# EPS_V1.net
KiCad netlist of a schematic drawn in Altium Designer
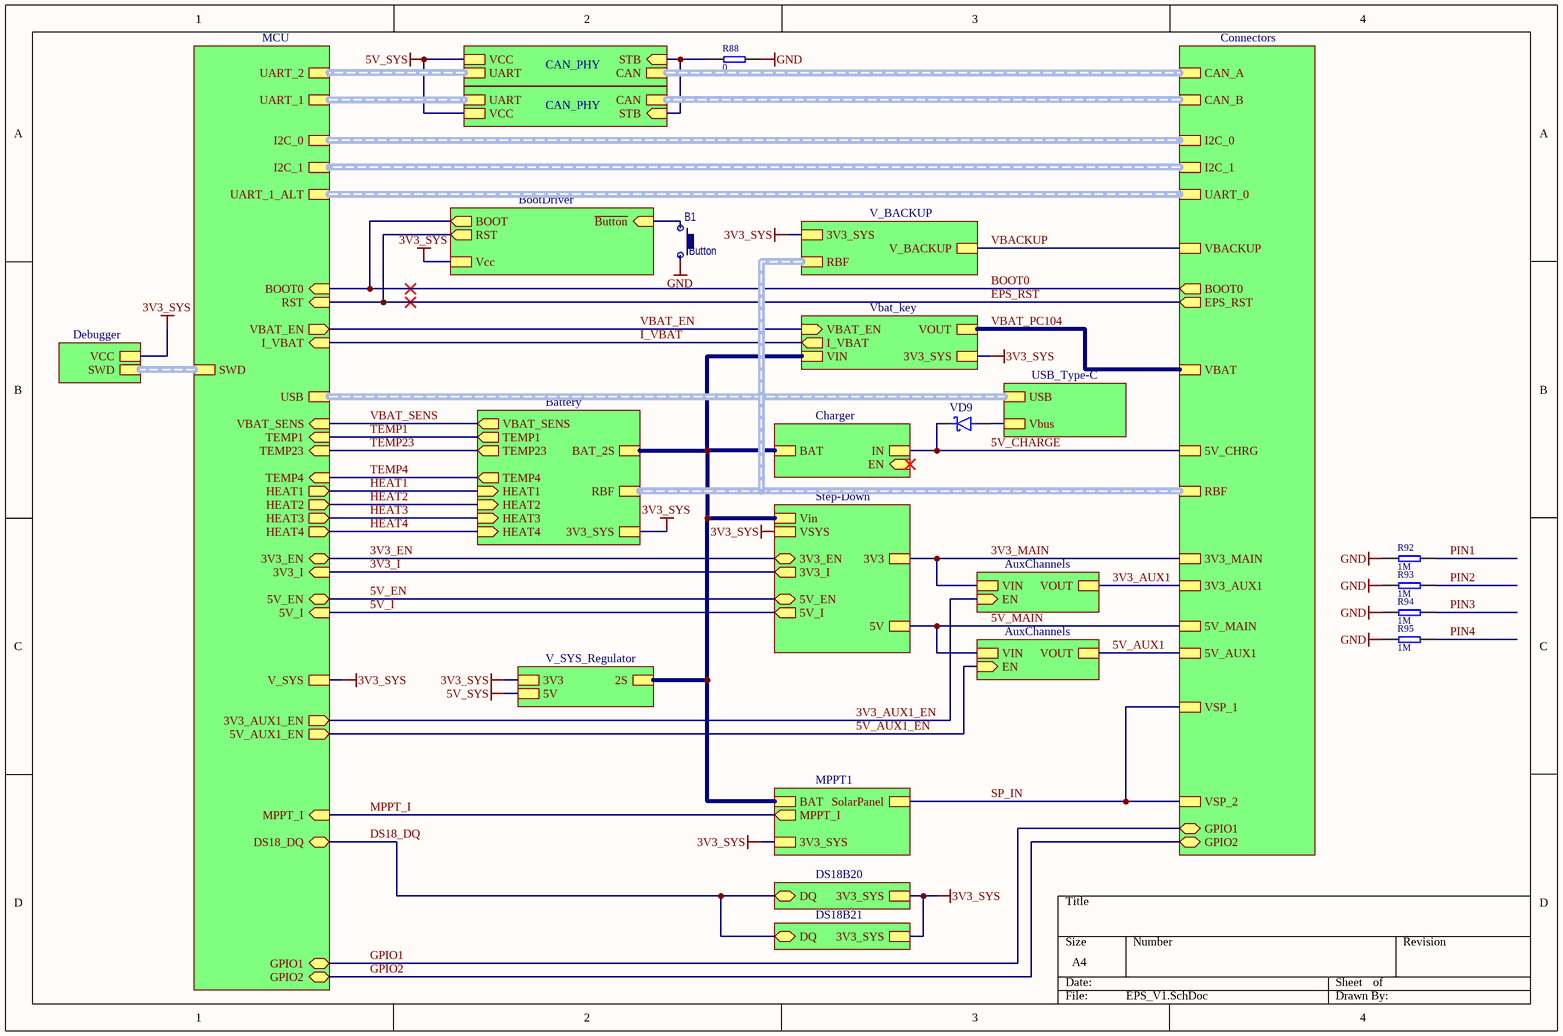
[diagram p0: EPS_V1.SchDoc]

(export (version "E")
  (design (tool "Eeschema 10.0.6"))
  (components
    (comp (ref "B1")
      (value "Button")
      (footprint "button")
      (libsource (lib "electromechanical") (part "Button"))
    )
    (comp (ref "R88")
      (value "0")
      (footprint "RES 0402")
      (description "Resistor")
      (fields (field (name "Comment") "RES 0402 0"))
      (libsource (lib "!main") (part "!Resistor"))
    )
    (comp (ref "R92")
      (value "1M")
      (footprint "RES 0402")
      (description "Resistor")
      (fields (field (name "Comment") "RES 0402 1M"))
      (libsource (lib "!main") (part "!Resistor"))
    )
    (comp (ref "R93")
      (value "1M")
      (footprint "RES 0402")
      (description "Resistor")
      (fields (field (name "Comment") "RES 0402 1M"))
      (libsource (lib "!main") (part "!Resistor"))
    )
    (comp (ref "R94")
      (value "1M")
      (footprint "RES 0402")
      (description "Resistor")
      (fields (field (name "Comment") "RES 0402 1M"))
      (libsource (lib "!main") (part "!Resistor"))
    )
    (comp (ref "R95")
      (value "1M")
      (footprint "RES 0402")
      (description "Resistor")
      (fields (field (name "Comment") "RES 0402 1M"))
      (libsource (lib "!main") (part "!Resistor"))
    )
    (comp (ref "VD9")
      (value "Shottly diode SOD-123")
      (footprint "SOD-123")
      (description "Diode Shottky")
      (libsource (lib "diodes") (part "DiodeS"))
    )
  )
  (nets
    (net (code "9") (name "/5V_CHARGE") (class "Default")
      (node (ref "VD9") (pin "C") (pinfunction "Cathode_C") (pintype "passive"))
    )
    (net (code "29") (name "/PIN1") (class "Default")
      (node (ref "R92") (pin "2") (pinfunction "12_2") (pintype "passive"))
    )
    (net (code "30") (name "/PIN2") (class "Default")
      (node (ref "R93") (pin "2") (pinfunction "12_2") (pintype "passive"))
    )
    (net (code "31") (name "/PIN3") (class "Default")
      (node (ref "R94") (pin "2") (pinfunction "12_2") (pintype "passive"))
    )
    (net (code "32") (name "/PIN4") (class "Default")
      (node (ref "R95") (pin "2") (pinfunction "12_2") (pintype "passive"))
    )
    (net (code "35") (name "/STB") (class "Default")
      (node (ref "R88") (pin "1") (pinfunction "11_1") (pintype "passive"))
    )
    (net (code "48") (name "/Vbus") (class "Default")
      (node (ref "VD9") (pin "A") (pinfunction "Anode_A") (pintype "passive"))
    )
    (net (code "49") (name "/~{Button}") (class "Default")
      (node (ref "B1") (pin "2") (pinfunction "2_2") (pintype "passive"))
    )
    (net (code "52") (name "GND") (class "Default")
      (node (ref "B1") (pin "1") (pinfunction "1_1") (pintype "passive"))
      (node (ref "R88") (pin "2") (pinfunction "12_2") (pintype "passive"))
      (node (ref "R92") (pin "1") (pinfunction "11_1") (pintype "passive"))
      (node (ref "R93") (pin "1") (pinfunction "11_1") (pintype "passive"))
      (node (ref "R94") (pin "1") (pinfunction "11_1") (pintype "passive"))
      (node (ref "R95") (pin "1") (pinfunction "11_1") (pintype "passive"))
    )
  )
)
